# AnalogueIsolatedReceiver.net
KiCad netlist of a schematic drawn in Altium Designer
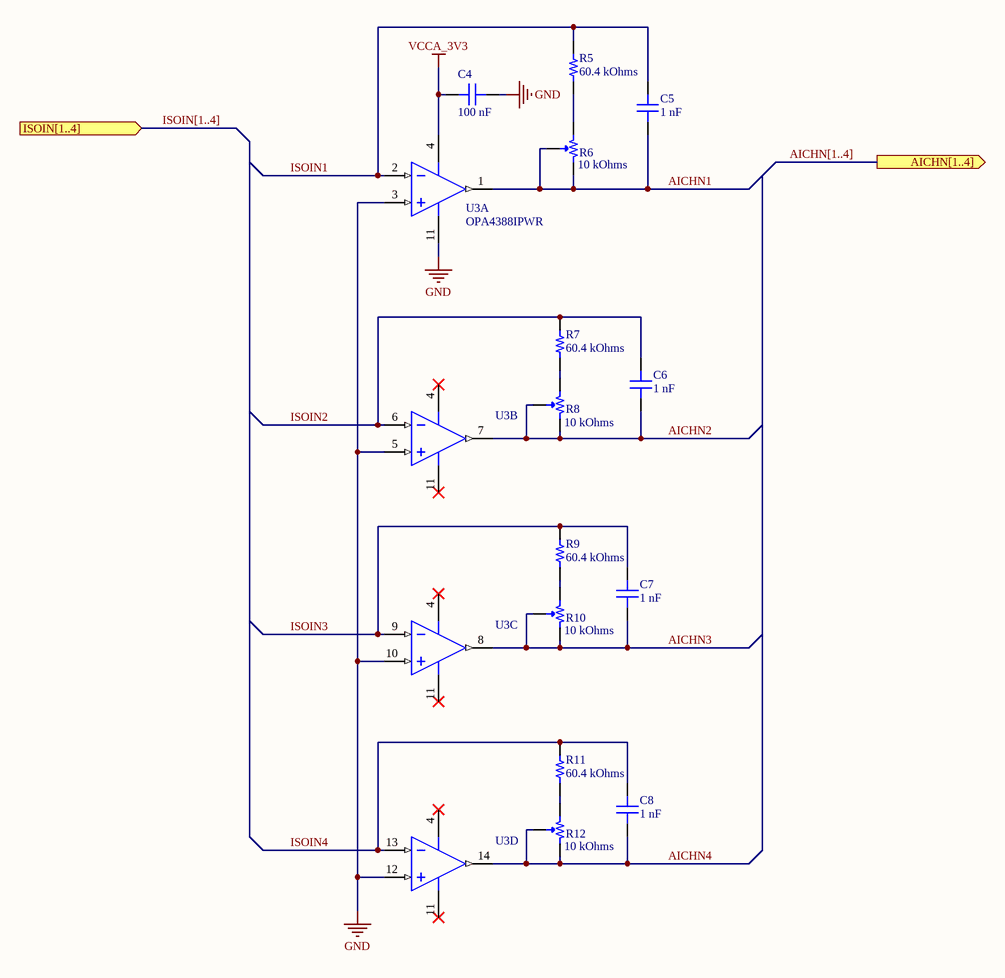
[diagram p0: AnalogueIsolatedReceiver.SchDoc]

(export (version "E")
  (design (tool "Eeschema 10.0.6"))
  (components
    (comp (ref "C4")
      (value "100 nF")
      (footprint "CAP 0603_1608")
      (description "MLCC Ceramic 100 nF 16 V 10% Capacitor")
      (fields (field (name "PART NUMBER") "0603YC104KAT2A") (field (name "MANUFACTURER") "AVX"))
      (libsource (lib "Database_Libs") (part "Capacitor"))
    )
    (comp (ref "C5")
      (value "1 nF")
      (footprint "CAP 0603_1608")
      (description "MLCC Ceramic 1 nF 10 V 5% Capacitor")
      (fields (field (name "PART NUMBER") "0603ZA102JAT4A") (field (name "MANUFACTURER") "AVX"))
      (libsource (lib "Database_Libs") (part "Capacitor"))
    )
    (comp (ref "C6")
      (value "1 nF")
      (footprint "CAP 0603_1608")
      (description "MLCC Ceramic 1 nF 10 V 5% Capacitor")
      (fields (field (name "PART NUMBER") "0603ZA102JAT4A") (field (name "MANUFACTURER") "AVX"))
      (libsource (lib "Database_Libs") (part "Capacitor"))
    )
    (comp (ref "C7")
      (value "1 nF")
      (footprint "CAP 0603_1608")
      (description "MLCC Ceramic 1 nF 10 V 5% Capacitor")
      (fields (field (name "PART NUMBER") "0603ZA102JAT4A") (field (name "MANUFACTURER") "AVX"))
      (libsource (lib "Database_Libs") (part "Capacitor"))
    )
    (comp (ref "C8")
      (value "1 nF")
      (footprint "CAP 0603_1608")
      (description "MLCC Ceramic 1 nF 10 V 5% Capacitor")
      (fields (field (name "PART NUMBER") "0603ZA102JAT4A") (field (name "MANUFACTURER") "AVX"))
      (libsource (lib "Database_Libs") (part "Capacitor"))
    )
    (comp (ref "R5")
      (value "60.4 kOhms")
      (footprint "RES 0603_1608")
      (description "Thin Film Resistor 60.4 kOhms 1%")
      (fields (field (name "PART NUMBER") "CRCW060360K4FKEA") (field (name "MANUFACTURER") "Vishay / Dale"))
      (libsource (lib "Database_Libs") (part "Resistor"))
    )
    (comp (ref "R6")
      (value "10 kOhms")
      (footprint "POT BOURNS TRIMPOT 3224W")
      (description "Inline Multitourn 10 kOhms 10% potentiometer")
      (fields (field (name "PART NUMBER") "3224W-1-103G") (field (name "MANUFACTURER") "Bourns"))
      (libsource (lib "Database_Libs") (part "Potentiometer"))
    )
    (comp (ref "R7")
      (value "60.4 kOhms")
      (footprint "RES 0603_1608")
      (description "Thin Film Resistor 60.4 kOhms 1%")
      (fields (field (name "PART NUMBER") "CRCW060360K4FKEA") (field (name "MANUFACTURER") "Vishay / Dale"))
      (libsource (lib "Database_Libs") (part "Resistor"))
    )
    (comp (ref "R8")
      (value "10 kOhms")
      (footprint "POT BOURNS TRIMPOT 3224W")
      (description "Inline Multitourn 10 kOhms 10% potentiometer")
      (fields (field (name "PART NUMBER") "3224W-1-103G") (field (name "MANUFACTURER") "Bourns"))
      (libsource (lib "Database_Libs") (part "Potentiometer"))
    )
    (comp (ref "R9")
      (value "60.4 kOhms")
      (footprint "RES 0603_1608")
      (description "Thin Film Resistor 60.4 kOhms 1%")
      (fields (field (name "PART NUMBER") "CRCW060360K4FKEA") (field (name "MANUFACTURER") "Vishay / Dale"))
      (libsource (lib "Database_Libs") (part "Resistor"))
    )
    (comp (ref "R10")
      (value "10 kOhms")
      (footprint "POT BOURNS TRIMPOT 3224W")
      (description "Inline Multitourn 10 kOhms 10% potentiometer")
      (fields (field (name "PART NUMBER") "3224W-1-103G") (field (name "MANUFACTURER") "Bourns"))
      (libsource (lib "Database_Libs") (part "Potentiometer"))
    )
    (comp (ref "R11")
      (value "60.4 kOhms")
      (footprint "RES 0603_1608")
      (description "Thin Film Resistor 60.4 kOhms 1%")
      (fields (field (name "PART NUMBER") "CRCW060360K4FKEA") (field (name "MANUFACTURER") "Vishay / Dale"))
      (libsource (lib "Database_Libs") (part "Resistor"))
    )
    (comp (ref "R12")
      (value "10 kOhms")
      (footprint "POT BOURNS TRIMPOT 3224W")
      (description "Inline Multitourn 10 kOhms 10% potentiometer")
      (fields (field (name "PART NUMBER") "3224W-1-103G") (field (name "MANUFACTURER") "Bourns"))
      (libsource (lib "Database_Libs") (part "Potentiometer"))
    )
    (comp (ref "U3")
      (value "OPA4388IPWR")
      (footprint "TI TSSOP-14 PW")
      (description "OPA4388 Zero-Drift, Zero-Crossover, Low Offset, Precision Rail-to-Rail I/O Opamp")
      (fields (field (name "MANUFACTURER") "Texas Instruments"))
      (libsource (lib "Database_Libs") (part "OPA4388"))
    )
  )
  (nets
    (net (code "1") (name "/AICHN1") (class "Default")
      (node (ref "C5") (pin "2") (pinfunction "2_2") (pintype "passive"))
      (node (ref "R6") (pin "2") (pinfunction "2_2") (pintype "passive"))
      (node (ref "R6") (pin "3") (pinfunction "3_3") (pintype "passive"))
      (node (ref "U3") (pin "1") (pinfunction "OUT1_1") (pintype "output"))
    )
    (net (code "2") (name "/AICHN2") (class "Default")
      (node (ref "C6") (pin "2") (pinfunction "2_2") (pintype "passive"))
      (node (ref "R8") (pin "2") (pinfunction "2_2") (pintype "passive"))
      (node (ref "R8") (pin "3") (pinfunction "3_3") (pintype "passive"))
      (node (ref "U3") (pin "7") (pinfunction "OUT2_7") (pintype "output"))
    )
    (net (code "3") (name "/AICHN3") (class "Default")
      (node (ref "C7") (pin "2") (pinfunction "2_2") (pintype "passive"))
      (node (ref "R10") (pin "2") (pinfunction "2_2") (pintype "passive"))
      (node (ref "R10") (pin "3") (pinfunction "3_3") (pintype "passive"))
      (node (ref "U3") (pin "8") (pinfunction "OUT3_8") (pintype "output"))
    )
    (net (code "4") (name "/AICHN4") (class "Default")
      (node (ref "C8") (pin "2") (pinfunction "2_2") (pintype "passive"))
      (node (ref "R12") (pin "2") (pinfunction "2_2") (pintype "passive"))
      (node (ref "R12") (pin "3") (pinfunction "3_3") (pintype "passive"))
      (node (ref "U3") (pin "14") (pinfunction "OUT4_14") (pintype "output"))
    )
    (net (code "6") (name "/ISOIN1") (class "Default")
      (node (ref "C5") (pin "1") (pinfunction "1_1") (pintype "passive"))
      (node (ref "R5") (pin "2") (pinfunction "2_2") (pintype "passive"))
      (node (ref "U3") (pin "2") (pinfunction "IN1-_2") (pintype "input"))
    )
    (net (code "7") (name "/ISOIN2") (class "Default")
      (node (ref "C6") (pin "1") (pinfunction "1_1") (pintype "passive"))
      (node (ref "R7") (pin "2") (pinfunction "2_2") (pintype "passive"))
      (node (ref "U3") (pin "6") (pinfunction "IN2-_6") (pintype "input"))
    )
    (net (code "8") (name "/ISOIN3") (class "Default")
      (node (ref "C7") (pin "1") (pinfunction "1_1") (pintype "passive"))
      (node (ref "R9") (pin "2") (pinfunction "2_2") (pintype "passive"))
      (node (ref "U3") (pin "9") (pinfunction "IN3-_9") (pintype "input"))
    )
    (net (code "9") (name "/ISOIN4") (class "Default")
      (node (ref "C8") (pin "1") (pinfunction "1_1") (pintype "passive"))
      (node (ref "R11") (pin "2") (pinfunction "2_2") (pintype "passive"))
      (node (ref "U3") (pin "13") (pinfunction "IN4-_13") (pintype "input"))
    )
    (net (code "11") (name "GND") (class "Default")
      (node (ref "C4") (pin "1") (pinfunction "1_1") (pintype "passive"))
      (node (ref "U3") (pin "10") (pinfunction "IN3+_10") (pintype "input"))
      (node (ref "U3") (pin "11") (pinfunction "GND_11") (pintype "power_in"))
      (node (ref "U3") (pin "12") (pinfunction "IN4+_12") (pintype "input"))
      (node (ref "U3") (pin "3") (pinfunction "IN1+_3") (pintype "input"))
      (node (ref "U3") (pin "5") (pinfunction "IN2+_5") (pintype "input"))
    )
    (net (code "12") (name "Net-(R5-Pad1)") (class "Default")
      (node (ref "R5") (pin "1") (pinfunction "1_1") (pintype "passive"))
      (node (ref "R6") (pin "1") (pinfunction "1_1") (pintype "passive"))
    )
    (net (code "13") (name "Net-(R7-Pad1)") (class "Default")
      (node (ref "R7") (pin "1") (pinfunction "1_1") (pintype "passive"))
      (node (ref "R8") (pin "1") (pinfunction "1_1") (pintype "passive"))
    )
    (net (code "14") (name "Net-(R10-Pad1)") (class "Default")
      (node (ref "R10") (pin "1") (pinfunction "1_1") (pintype "passive"))
      (node (ref "R9") (pin "1") (pinfunction "1_1") (pintype "passive"))
    )
    (net (code "15") (name "Net-(R11-Pad1)") (class "Default")
      (node (ref "R11") (pin "1") (pinfunction "1_1") (pintype "passive"))
      (node (ref "R12") (pin "1") (pinfunction "1_1") (pintype "passive"))
    )
    (net (code "16") (name "VCCA_3V3") (class "Default")
      (node (ref "C4") (pin "2") (pinfunction "2_2") (pintype "passive"))
      (node (ref "U3") (pin "4") (pinfunction "VDD_4") (pintype "power_in"))
    )
    (net (code "17") (name "unconnected-(U3B-GND-Pad11)") (class "Default")
      (node (ref "U3") (pin "11") (pinfunction "GND_11") (pintype "power_in+no_connect"))
    )
    (net (code "18") (name "unconnected-(U3B-VDD-Pad4)") (class "Default")
      (node (ref "U3") (pin "4") (pinfunction "VDD_4") (pintype "power_in+no_connect"))
    )
    (net (code "19") (name "unconnected-(U3C-GND-Pad11)") (class "Default")
      (node (ref "U3") (pin "11") (pinfunction "GND_11") (pintype "power_in+no_connect"))
    )
    (net (code "20") (name "unconnected-(U3C-VDD-Pad4)") (class "Default")
      (node (ref "U3") (pin "4") (pinfunction "VDD_4") (pintype "power_in+no_connect"))
    )
    (net (code "21") (name "unconnected-(U3D-GND-Pad11)") (class "Default")
      (node (ref "U3") (pin "11") (pinfunction "GND_11") (pintype "power_in+no_connect"))
    )
    (net (code "22") (name "unconnected-(U3D-VDD-Pad4)") (class "Default")
      (node (ref "U3") (pin "4") (pinfunction "VDD_4") (pintype "power_in+no_connect"))
    )
  )
)
